# fire-alarm-schema-electrica.net
KiCad netlist of a schematic drawn in EAGLE
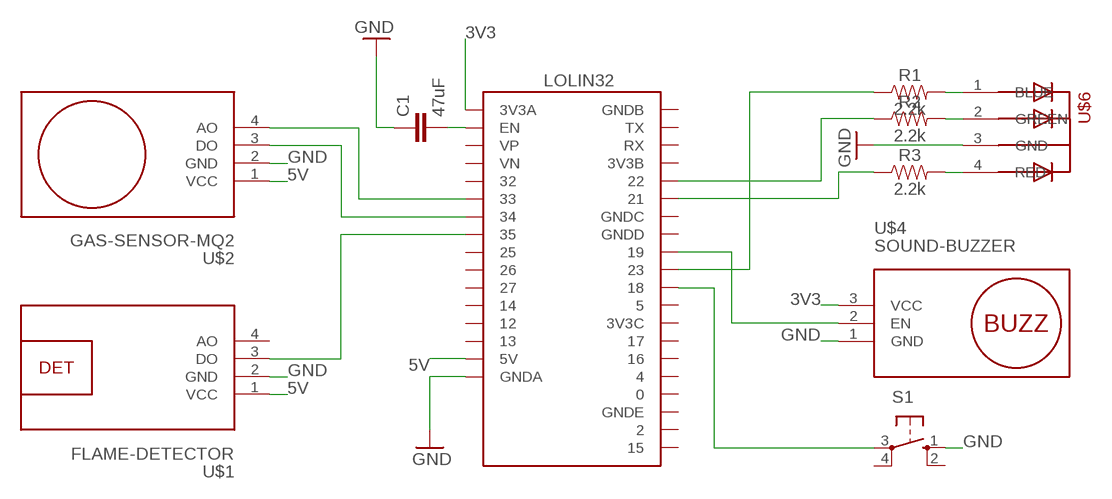
[diagram p0: schematic, sheet 1]

(export (version "E")
  (design (tool "Eeschema 10.0.6"))
  (components
    (comp (ref "C1")
      (value "47uF")
      (footprint "eagle-import:0603")
      (libsource (lib "eagle-import") (part "10UF-0603-6.3V-20%"))
    )
    (comp (ref "LOLIN32")
      (value "SSFD_LOLIN32_WEMOS_CHINA_W_BATT")
      (footprint "eagle-import:SSFD_LOLIN32_WEMOS_CHINA_W_BATT")
      (libsource (lib "eagle-import") (part "SSFD_LOLIN32_WEMOS_CHINA_W_BATT"))
    )
    (comp (ref "R1")
      (value "2.2k")
      (footprint "eagle-import:0603")
      (libsource (lib "eagle-import") (part "2.2KOHM-0603-1/10W-1%"))
    )
    (comp (ref "R2")
      (value "2.2k")
      (footprint "eagle-import:0603")
      (libsource (lib "eagle-import") (part "2.2KOHM-0603-1/10W-1%"))
    )
    (comp (ref "R3")
      (value "2.2k")
      (footprint "eagle-import:0603")
      (libsource (lib "eagle-import") (part "2.2KOHM-0603-1/10W-1%"))
    )
    (comp (ref "S1")
      (value "10-XX")
      (footprint "eagle-import:B3F-10XX")
      (fields (field (name "MPN") "B3F-1000"))
      (libsource (lib "eagle-import") (part "10-XX"))
    )
    (comp (ref "U$1")
      (value "FLAME-DETECTOR")
      (footprint "eagle-import:FLAME-DETECTOR")
      (libsource (lib "eagle-import") (part "FLAME-DETECTOR"))
    )
    (comp (ref "U$2")
      (value "GAS-SENSOR-MQ2")
      (footprint "eagle-import:GAS-SENSOR-MQ2")
      (libsource (lib "eagle-import") (part "GAS-SENSOR-MQ2"))
    )
    (comp (ref "U$4")
      (value "SOUND-BUZZER")
      (footprint "eagle-import:SOUND-BUZZER")
      (libsource (lib "eagle-import") (part "SOUND-BUZZER"))
    )
    (comp (ref "U$6")
      (value "5MMRGBLED")
      (footprint "eagle-import:LED5MMRGB")
      (libsource (lib "eagle-import") (part "5MMRGBLED"))
    )
  )
  (nets
    (net (code "1") (name "/3V3") (class "Default")
      (node (ref "LOLIN32") (pin "3V3A") (pinfunction "3V3A_3V3A") (pintype "bidirectional"))
      (node (ref "U$4") (pin "3") (pinfunction "VCC_3") (pintype "power_in"))
    )
    (net (code "2") (name "/5V") (class "Default")
      (node (ref "LOLIN32") (pin "5V") (pinfunction "5V_5V") (pintype "bidirectional"))
      (node (ref "U$1") (pin "1") (pinfunction "VCC_1") (pintype "power_in"))
      (node (ref "U$2") (pin "1") (pinfunction "VCC_1") (pintype "power_in"))
    )
    (net (code "3") (name "GND") (class "Default")
      (node (ref "C1") (pin "1") (pinfunction "1_1") (pintype "passive"))
      (node (ref "LOLIN32") (pin "GNDA") (pinfunction "GNDA_GNDA") (pintype "bidirectional"))
      (node (ref "S1") (pin "1") (pinfunction "S_1") (pintype "passive"))
      (node (ref "U$1") (pin "2") (pinfunction "GND_2") (pintype "power_in"))
      (node (ref "U$2") (pin "2") (pinfunction "GND_2") (pintype "power_in"))
      (node (ref "U$4") (pin "1") (pinfunction "GND_1") (pintype "power_in"))
      (node (ref "U$6") (pin "3") (pinfunction "GND_3") (pintype "bidirectional"))
    )
    (net (code "4") (name "Net-(C1-Pad2)") (class "Default")
      (node (ref "C1") (pin "2") (pinfunction "2_2") (pintype "passive"))
      (node (ref "LOLIN32") (pin "EN") (pinfunction "EN_EN") (pintype "bidirectional"))
    )
    (net (code "5") (name "Net-(LOLIN32-Pad21)") (class "Default")
      (node (ref "LOLIN32") (pin "21") (pinfunction "21_21") (pintype "bidirectional"))
      (node (ref "R3") (pin "1") (pinfunction "1_1") (pintype "passive"))
    )
    (net (code "6") (name "Net-(LOLIN32-Pad22)") (class "Default")
      (node (ref "LOLIN32") (pin "22") (pinfunction "22_22") (pintype "bidirectional"))
      (node (ref "R2") (pin "1") (pinfunction "1_1") (pintype "passive"))
    )
    (net (code "7") (name "Net-(LOLIN32-Pad23)") (class "Default")
      (node (ref "LOLIN32") (pin "23") (pinfunction "23_23") (pintype "bidirectional"))
      (node (ref "R1") (pin "1") (pinfunction "1_1") (pintype "passive"))
    )
    (net (code "8") (name "Net-(S1-P)") (class "Default")
      (node (ref "LOLIN32") (pin "18") (pinfunction "18_18") (pintype "bidirectional"))
      (node (ref "S1") (pin "3") (pinfunction "P_3") (pintype "passive"))
    )
    (net (code "9") (name "Net-(U$1-DO)") (class "Default")
      (node (ref "LOLIN32") (pin "35") (pinfunction "35_35") (pintype "bidirectional"))
      (node (ref "U$1") (pin "3") (pinfunction "DO_3") (pintype "bidirectional"))
    )
    (net (code "10") (name "Net-(U$2-AO)") (class "Default")
      (node (ref "LOLIN32") (pin "33") (pinfunction "33_33") (pintype "bidirectional"))
      (node (ref "U$2") (pin "4") (pinfunction "AO_4") (pintype "output"))
    )
    (net (code "11") (name "Net-(U$2-DO)") (class "Default")
      (node (ref "LOLIN32") (pin "34") (pinfunction "34_34") (pintype "bidirectional"))
      (node (ref "U$2") (pin "3") (pinfunction "DO_3") (pintype "output"))
    )
    (net (code "12") (name "Net-(U$4-EN)") (class "Default")
      (node (ref "LOLIN32") (pin "19") (pinfunction "19_19") (pintype "bidirectional"))
      (node (ref "U$4") (pin "2") (pinfunction "EN_2") (pintype "input"))
    )
    (net (code "13") (name "Net-(U$6-BLUE)") (class "Default")
      (node (ref "R1") (pin "2") (pinfunction "2_2") (pintype "passive"))
      (node (ref "U$6") (pin "1") (pinfunction "BLUE_1") (pintype "bidirectional"))
    )
    (net (code "14") (name "Net-(U$6-GREEN)") (class "Default")
      (node (ref "R2") (pin "2") (pinfunction "2_2") (pintype "passive"))
      (node (ref "U$6") (pin "2") (pinfunction "GREEN_2") (pintype "bidirectional"))
    )
    (net (code "15") (name "Net-(U$6-RED)") (class "Default")
      (node (ref "R3") (pin "2") (pinfunction "2_2") (pintype "passive"))
      (node (ref "U$6") (pin "4") (pinfunction "RED_4") (pintype "bidirectional"))
    )
    (net (code "16") (name "unconnected-(LOLIN32-Pad0)") (class "Default")
      (node (ref "LOLIN32") (pin "0") (pinfunction "0_0") (pintype "bidirectional"))
    )
    (net (code "17") (name "unconnected-(LOLIN32-Pad2)") (class "Default")
      (node (ref "LOLIN32") (pin "2") (pinfunction "2_2") (pintype "bidirectional"))
    )
    (net (code "18") (name "unconnected-(LOLIN32-Pad3V3B)") (class "Default")
      (node (ref "LOLIN32") (pin "3V3B") (pinfunction "3V3B_3V3B") (pintype "bidirectional"))
    )
    (net (code "19") (name "unconnected-(LOLIN32-Pad3V3C)") (class "Default")
      (node (ref "LOLIN32") (pin "3V3C") (pinfunction "3V3C_3V3C") (pintype "bidirectional"))
    )
    (net (code "20") (name "unconnected-(LOLIN32-Pad4)") (class "Default")
      (node (ref "LOLIN32") (pin "4") (pinfunction "4_4") (pintype "bidirectional"))
    )
    (net (code "21") (name "unconnected-(LOLIN32-Pad5)") (class "Default")
      (node (ref "LOLIN32") (pin "5") (pinfunction "5_5") (pintype "bidirectional"))
    )
    (net (code "22") (name "unconnected-(LOLIN32-Pad12)") (class "Default")
      (node (ref "LOLIN32") (pin "12") (pinfunction "12_12") (pintype "bidirectional"))
    )
    (net (code "23") (name "unconnected-(LOLIN32-Pad13)") (class "Default")
      (node (ref "LOLIN32") (pin "13") (pinfunction "13_13") (pintype "bidirectional"))
    )
    (net (code "24") (name "unconnected-(LOLIN32-Pad14)") (class "Default")
      (node (ref "LOLIN32") (pin "14") (pinfunction "14_14") (pintype "bidirectional"))
    )
    (net (code "25") (name "unconnected-(LOLIN32-Pad15)") (class "Default")
      (node (ref "LOLIN32") (pin "15") (pinfunction "15_15") (pintype "bidirectional"))
    )
    (net (code "26") (name "unconnected-(LOLIN32-Pad16)") (class "Default")
      (node (ref "LOLIN32") (pin "16") (pinfunction "16_16") (pintype "bidirectional"))
    )
    (net (code "27") (name "unconnected-(LOLIN32-Pad17)") (class "Default")
      (node (ref "LOLIN32") (pin "17") (pinfunction "17_17") (pintype "bidirectional"))
    )
    (net (code "28") (name "unconnected-(LOLIN32-Pad25)") (class "Default")
      (node (ref "LOLIN32") (pin "25") (pinfunction "25_25") (pintype "bidirectional"))
    )
    (net (code "29") (name "unconnected-(LOLIN32-Pad26)") (class "Default")
      (node (ref "LOLIN32") (pin "26") (pinfunction "26_26") (pintype "bidirectional"))
    )
    (net (code "30") (name "unconnected-(LOLIN32-Pad27)") (class "Default")
      (node (ref "LOLIN32") (pin "27") (pinfunction "27_27") (pintype "bidirectional"))
    )
    (net (code "31") (name "unconnected-(LOLIN32-Pad32)") (class "Default")
      (node (ref "LOLIN32") (pin "32") (pinfunction "32_32") (pintype "bidirectional"))
    )
    (net (code "32") (name "unconnected-(LOLIN32-PadGNDB)") (class "Default")
      (node (ref "LOLIN32") (pin "GNDB") (pinfunction "GNDB_GNDB") (pintype "bidirectional"))
    )
    (net (code "33") (name "unconnected-(LOLIN32-PadGNDC)") (class "Default")
      (node (ref "LOLIN32") (pin "GNDC") (pinfunction "GNDC_GNDC") (pintype "bidirectional"))
    )
    (net (code "34") (name "unconnected-(LOLIN32-PadGNDD)") (class "Default")
      (node (ref "LOLIN32") (pin "GNDD") (pinfunction "GNDD_GNDD") (pintype "bidirectional"))
    )
    (net (code "35") (name "unconnected-(LOLIN32-PadGNDE)") (class "Default")
      (node (ref "LOLIN32") (pin "GNDE") (pinfunction "GNDE_GNDE") (pintype "bidirectional"))
    )
    (net (code "36") (name "unconnected-(LOLIN32-PadRX)") (class "Default")
      (node (ref "LOLIN32") (pin "RX") (pinfunction "RX_RX") (pintype "bidirectional"))
    )
    (net (code "37") (name "unconnected-(LOLIN32-PadTX)") (class "Default")
      (node (ref "LOLIN32") (pin "TX") (pinfunction "TX_TX") (pintype "bidirectional"))
    )
    (net (code "38") (name "unconnected-(LOLIN32-PadVN)") (class "Default")
      (node (ref "LOLIN32") (pin "VN") (pinfunction "VN_VN") (pintype "bidirectional"))
    )
    (net (code "39") (name "unconnected-(LOLIN32-PadVP)") (class "Default")
      (node (ref "LOLIN32") (pin "VP") (pinfunction "VP_VP") (pintype "bidirectional"))
    )
    (net (code "40") (name "unconnected-(S1-P1-Pad4)") (class "Default")
      (node (ref "S1") (pin "4") (pinfunction "P1_4") (pintype "passive"))
    )
    (net (code "41") (name "unconnected-(S1-S1-Pad2)") (class "Default")
      (node (ref "S1") (pin "2") (pinfunction "S1_2") (pintype "passive"))
    )
    (net (code "42") (name "unconnected-(U$1-AO-Pad4)") (class "Default")
      (node (ref "U$1") (pin "4") (pinfunction "AO_4") (pintype "bidirectional"))
    )
  )
)
